# DenScript_5x5_Prototyping_Board_V1_0.net
KiCad netlist of a schematic drawn in EAGLE
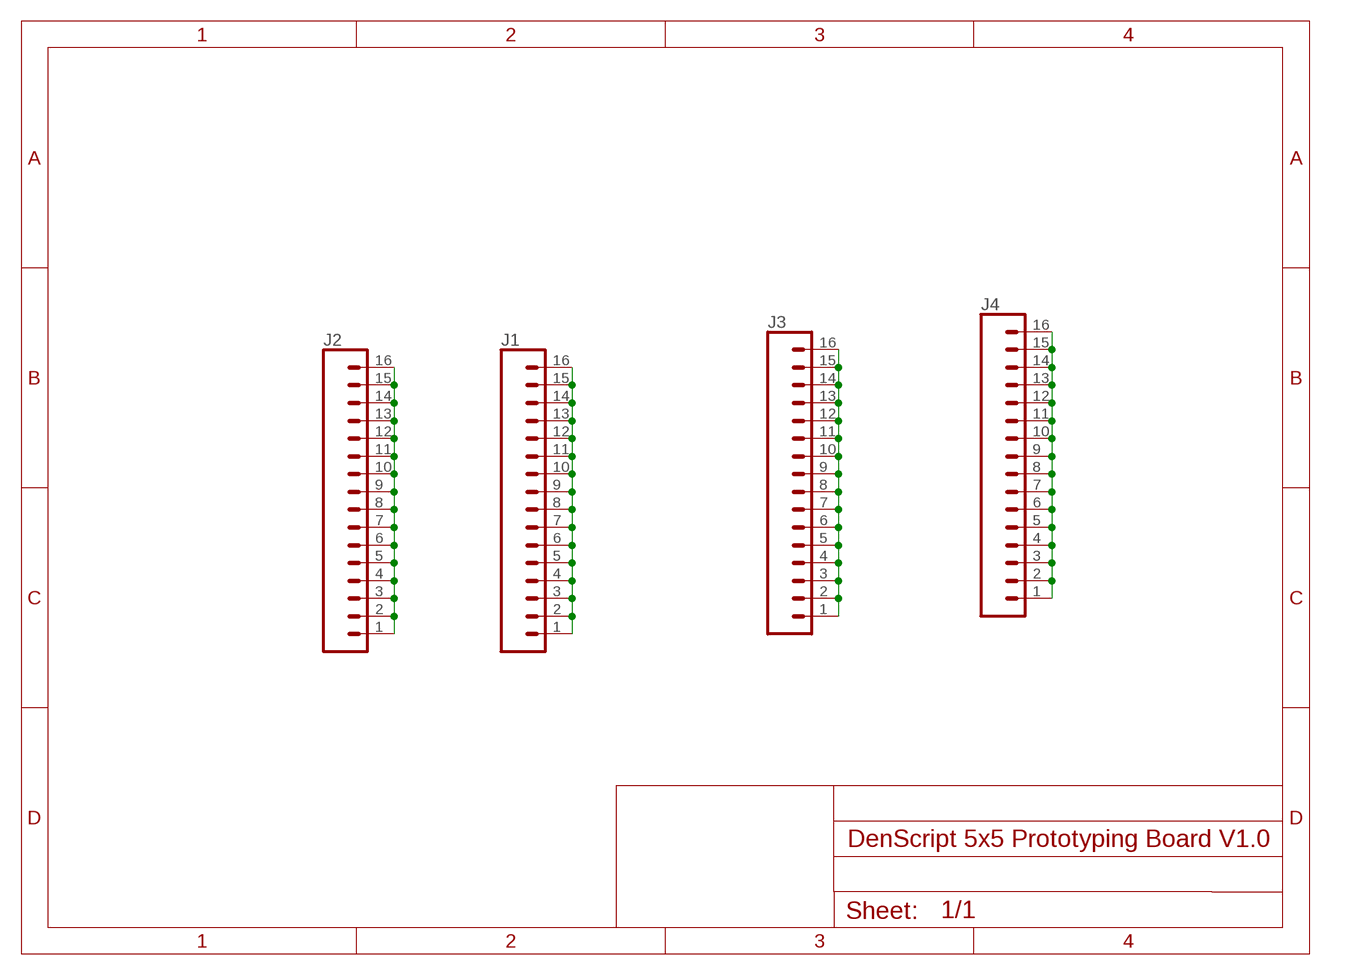
[diagram p0: schematic, sheet 1]

(export (version "E")
  (design (tool "Eeschema 10.0.6"))
  (components
    (comp (ref "J1")
      (value "CONN_16")
      (footprint "eagle-import:1X16")
      (libsource (lib "eagle-import") (part "CONN_16"))
    )
    (comp (ref "J2")
      (value "CONN_16")
      (footprint "eagle-import:1X16")
      (libsource (lib "eagle-import") (part "CONN_16"))
    )
    (comp (ref "J3")
      (value "CONN_16")
      (footprint "eagle-import:1X16")
      (libsource (lib "eagle-import") (part "CONN_16"))
    )
    (comp (ref "J4")
      (value "CONN_16")
      (footprint "eagle-import:1X16")
      (libsource (lib "eagle-import") (part "CONN_16"))
    )
  )
  (nets
    (net (code "1") (name "Net-(J1-Pad1)") (class "Default")
      (node (ref "J1") (pin "1") (pinfunction "1_1") (pintype "passive"))
      (node (ref "J1") (pin "10") (pinfunction "10_10") (pintype "passive"))
      (node (ref "J1") (pin "11") (pinfunction "11_11") (pintype "passive"))
      (node (ref "J1") (pin "12") (pinfunction "12_12") (pintype "passive"))
      (node (ref "J1") (pin "13") (pinfunction "13_13") (pintype "passive"))
      (node (ref "J1") (pin "14") (pinfunction "14_14") (pintype "passive"))
      (node (ref "J1") (pin "15") (pinfunction "15_15") (pintype "passive"))
      (node (ref "J1") (pin "16") (pinfunction "16_16") (pintype "passive"))
      (node (ref "J1") (pin "2") (pinfunction "2_2") (pintype "passive"))
      (node (ref "J1") (pin "3") (pinfunction "3_3") (pintype "passive"))
      (node (ref "J1") (pin "4") (pinfunction "4_4") (pintype "passive"))
      (node (ref "J1") (pin "5") (pinfunction "5_5") (pintype "passive"))
      (node (ref "J1") (pin "6") (pinfunction "6_6") (pintype "passive"))
      (node (ref "J1") (pin "7") (pinfunction "7_7") (pintype "passive"))
      (node (ref "J1") (pin "8") (pinfunction "8_8") (pintype "passive"))
      (node (ref "J1") (pin "9") (pinfunction "9_9") (pintype "passive"))
    )
    (net (code "2") (name "Net-(J2-Pad1)") (class "Default")
      (node (ref "J2") (pin "1") (pinfunction "1_1") (pintype "passive"))
      (node (ref "J2") (pin "10") (pinfunction "10_10") (pintype "passive"))
      (node (ref "J2") (pin "11") (pinfunction "11_11") (pintype "passive"))
      (node (ref "J2") (pin "12") (pinfunction "12_12") (pintype "passive"))
      (node (ref "J2") (pin "13") (pinfunction "13_13") (pintype "passive"))
      (node (ref "J2") (pin "14") (pinfunction "14_14") (pintype "passive"))
      (node (ref "J2") (pin "15") (pinfunction "15_15") (pintype "passive"))
      (node (ref "J2") (pin "16") (pinfunction "16_16") (pintype "passive"))
      (node (ref "J2") (pin "2") (pinfunction "2_2") (pintype "passive"))
      (node (ref "J2") (pin "3") (pinfunction "3_3") (pintype "passive"))
      (node (ref "J2") (pin "4") (pinfunction "4_4") (pintype "passive"))
      (node (ref "J2") (pin "5") (pinfunction "5_5") (pintype "passive"))
      (node (ref "J2") (pin "6") (pinfunction "6_6") (pintype "passive"))
      (node (ref "J2") (pin "7") (pinfunction "7_7") (pintype "passive"))
      (node (ref "J2") (pin "8") (pinfunction "8_8") (pintype "passive"))
      (node (ref "J2") (pin "9") (pinfunction "9_9") (pintype "passive"))
    )
    (net (code "3") (name "Net-(J3-Pad1)") (class "Default")
      (node (ref "J3") (pin "1") (pinfunction "1_1") (pintype "passive"))
      (node (ref "J3") (pin "10") (pinfunction "10_10") (pintype "passive"))
      (node (ref "J3") (pin "11") (pinfunction "11_11") (pintype "passive"))
      (node (ref "J3") (pin "12") (pinfunction "12_12") (pintype "passive"))
      (node (ref "J3") (pin "13") (pinfunction "13_13") (pintype "passive"))
      (node (ref "J3") (pin "14") (pinfunction "14_14") (pintype "passive"))
      (node (ref "J3") (pin "15") (pinfunction "15_15") (pintype "passive"))
      (node (ref "J3") (pin "16") (pinfunction "16_16") (pintype "passive"))
      (node (ref "J3") (pin "2") (pinfunction "2_2") (pintype "passive"))
      (node (ref "J3") (pin "3") (pinfunction "3_3") (pintype "passive"))
      (node (ref "J3") (pin "4") (pinfunction "4_4") (pintype "passive"))
      (node (ref "J3") (pin "5") (pinfunction "5_5") (pintype "passive"))
      (node (ref "J3") (pin "6") (pinfunction "6_6") (pintype "passive"))
      (node (ref "J3") (pin "7") (pinfunction "7_7") (pintype "passive"))
      (node (ref "J3") (pin "8") (pinfunction "8_8") (pintype "passive"))
      (node (ref "J3") (pin "9") (pinfunction "9_9") (pintype "passive"))
    )
    (net (code "4") (name "Net-(J4-Pad1)") (class "Default")
      (node (ref "J4") (pin "1") (pinfunction "1_1") (pintype "passive"))
      (node (ref "J4") (pin "10") (pinfunction "10_10") (pintype "passive"))
      (node (ref "J4") (pin "11") (pinfunction "11_11") (pintype "passive"))
      (node (ref "J4") (pin "12") (pinfunction "12_12") (pintype "passive"))
      (node (ref "J4") (pin "13") (pinfunction "13_13") (pintype "passive"))
      (node (ref "J4") (pin "14") (pinfunction "14_14") (pintype "passive"))
      (node (ref "J4") (pin "15") (pinfunction "15_15") (pintype "passive"))
      (node (ref "J4") (pin "16") (pinfunction "16_16") (pintype "passive"))
      (node (ref "J4") (pin "2") (pinfunction "2_2") (pintype "passive"))
      (node (ref "J4") (pin "3") (pinfunction "3_3") (pintype "passive"))
      (node (ref "J4") (pin "4") (pinfunction "4_4") (pintype "passive"))
      (node (ref "J4") (pin "5") (pinfunction "5_5") (pintype "passive"))
      (node (ref "J4") (pin "6") (pinfunction "6_6") (pintype "passive"))
      (node (ref "J4") (pin "7") (pinfunction "7_7") (pintype "passive"))
      (node (ref "J4") (pin "8") (pinfunction "8_8") (pintype "passive"))
      (node (ref "J4") (pin "9") (pinfunction "9_9") (pintype "passive"))
    )
  )
)
